# button_board_v0_3_2.net
KiCad netlist of a schematic drawn in EAGLE
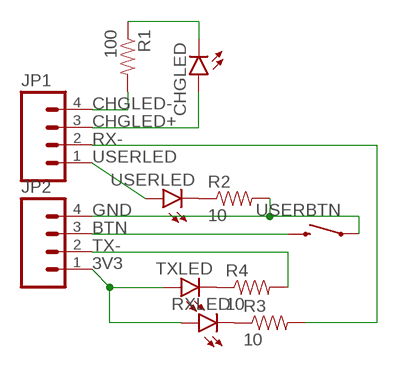
[diagram p0: schematic, sheet 1]

(export (version "E")
  (design (tool "Eeschema 10.0.6"))
  (components
    (comp (ref "CHGLED")
      (value "LED-FKIT-1206")
      (footprint "eagle-import:FKIT-LED-1206")
      (libsource (lib "eagle-import") (part "LED-FKIT-1206"))
    )
    (comp (ref "JP1")
      (value "M04PTH")
      (footprint "eagle-import:1X04")
      (libsource (lib "eagle-import") (part "M04PTH"))
    )
    (comp (ref "JP2")
      (value "M04PTH")
      (footprint "eagle-import:1X04")
      (libsource (lib "eagle-import") (part "M04PTH"))
    )
    (comp (ref "R1")
      (value "100")
      (footprint "eagle-import:0603-RES")
      (libsource (lib "eagle-import") (part "RESISTOR0603-RES"))
    )
    (comp (ref "R2")
      (value "10")
      (footprint "eagle-import:0603-RES")
      (libsource (lib "eagle-import") (part "RESISTOR0603-RES"))
    )
    (comp (ref "R3")
      (value "10")
      (footprint "eagle-import:0603-RES")
      (libsource (lib "eagle-import") (part "RESISTOR0603-RES"))
    )
    (comp (ref "R4")
      (value "10")
      (footprint "eagle-import:0603-RES")
      (libsource (lib "eagle-import") (part "RESISTOR0603-RES"))
    )
    (comp (ref "RXLED")
      (value "LED-FKIT-1206")
      (footprint "eagle-import:FKIT-LED-1206")
      (libsource (lib "eagle-import") (part "LED-FKIT-1206"))
    )
    (comp (ref "TXLED")
      (value "LED-FKIT-1206")
      (footprint "eagle-import:FKIT-LED-1206")
      (libsource (lib "eagle-import") (part "LED-FKIT-1206"))
    )
    (comp (ref "USERBTN")
      (value "SWITCH-MOMENTARY-2PCB_MOUNTSMD_OMRON_B3S_100X")
      (footprint "eagle-import:TACTILE_SWITCH_LARGE")
      (libsource (lib "eagle-import") (part "SWITCH-MOMENTARY-2SMD_OMRON_B3S_100XPCB_MOUNT"))
    )
    (comp (ref "USERLED")
      (value "LED-FKIT-1206")
      (footprint "eagle-import:FKIT-LED-1206")
      (libsource (lib "eagle-import") (part "LED-FKIT-1206"))
    )
  )
  (nets
    (net (code "1") (name "/3V3") (class "Default")
      (node (ref "JP2") (pin "1") (pinfunction "1_1") (pintype "passive"))
      (node (ref "RXLED") (pin "A") (pinfunction "A_A") (pintype "passive"))
      (node (ref "TXLED") (pin "A") (pinfunction "A_A") (pintype "passive"))
    )
    (net (code "2") (name "/BTN") (class "Default")
      (node (ref "JP2") (pin "3") (pinfunction "3_3") (pintype "passive"))
      (node (ref "USERBTN") (pin "3") (pinfunction "2_3") (pintype "passive"))
      (node (ref "USERBTN") (pin "4") (pinfunction "2_4") (pintype "passive"))
    )
    (net (code "3") (name "/CHGLED+") (class "Default")
      (node (ref "CHGLED") (pin "A") (pinfunction "A_A") (pintype "passive"))
      (node (ref "JP1") (pin "3") (pinfunction "3_3") (pintype "passive"))
    )
    (net (code "4") (name "/CHGLED-") (class "Default")
      (node (ref "JP1") (pin "4") (pinfunction "4_4") (pintype "passive"))
      (node (ref "R1") (pin "2") (pinfunction "2_2") (pintype "passive"))
    )
    (net (code "5") (name "/GND") (class "Default")
      (node (ref "JP2") (pin "4") (pinfunction "4_4") (pintype "passive"))
      (node (ref "R2") (pin "2") (pinfunction "2_2") (pintype "passive"))
      (node (ref "USERBTN") (pin "1") (pinfunction "1_1") (pintype "passive"))
      (node (ref "USERBTN") (pin "2") (pinfunction "1_2") (pintype "passive"))
    )
    (net (code "6") (name "/RX-") (class "Default")
      (node (ref "JP1") (pin "2") (pinfunction "2_2") (pintype "passive"))
      (node (ref "R3") (pin "2") (pinfunction "2_2") (pintype "passive"))
    )
    (net (code "7") (name "/TX-") (class "Default")
      (node (ref "JP2") (pin "2") (pinfunction "2_2") (pintype "passive"))
      (node (ref "R4") (pin "2") (pinfunction "2_2") (pintype "passive"))
    )
    (net (code "8") (name "/USERLED") (class "Default")
      (node (ref "JP1") (pin "1") (pinfunction "1_1") (pintype "passive"))
      (node (ref "USERLED") (pin "A") (pinfunction "A_A") (pintype "passive"))
    )
    (net (code "9") (name "Net-(CHGLED-PadC)") (class "Default")
      (node (ref "CHGLED") (pin "C") (pinfunction "C_C") (pintype "passive"))
      (node (ref "R1") (pin "1") (pinfunction "1_1") (pintype "passive"))
    )
    (net (code "10") (name "Net-(R2-Pad1)") (class "Default")
      (node (ref "R2") (pin "1") (pinfunction "1_1") (pintype "passive"))
      (node (ref "USERLED") (pin "C") (pinfunction "C_C") (pintype "passive"))
    )
    (net (code "11") (name "Net-(R3-Pad1)") (class "Default")
      (node (ref "R3") (pin "1") (pinfunction "1_1") (pintype "passive"))
      (node (ref "RXLED") (pin "C") (pinfunction "C_C") (pintype "passive"))
    )
    (net (code "12") (name "Net-(R4-Pad1)") (class "Default")
      (node (ref "R4") (pin "1") (pinfunction "1_1") (pintype "passive"))
      (node (ref "TXLED") (pin "C") (pinfunction "C_C") (pintype "passive"))
    )
  )
)
